# HBSTICK.net
KiCad netlist of a schematic drawn in EAGLE
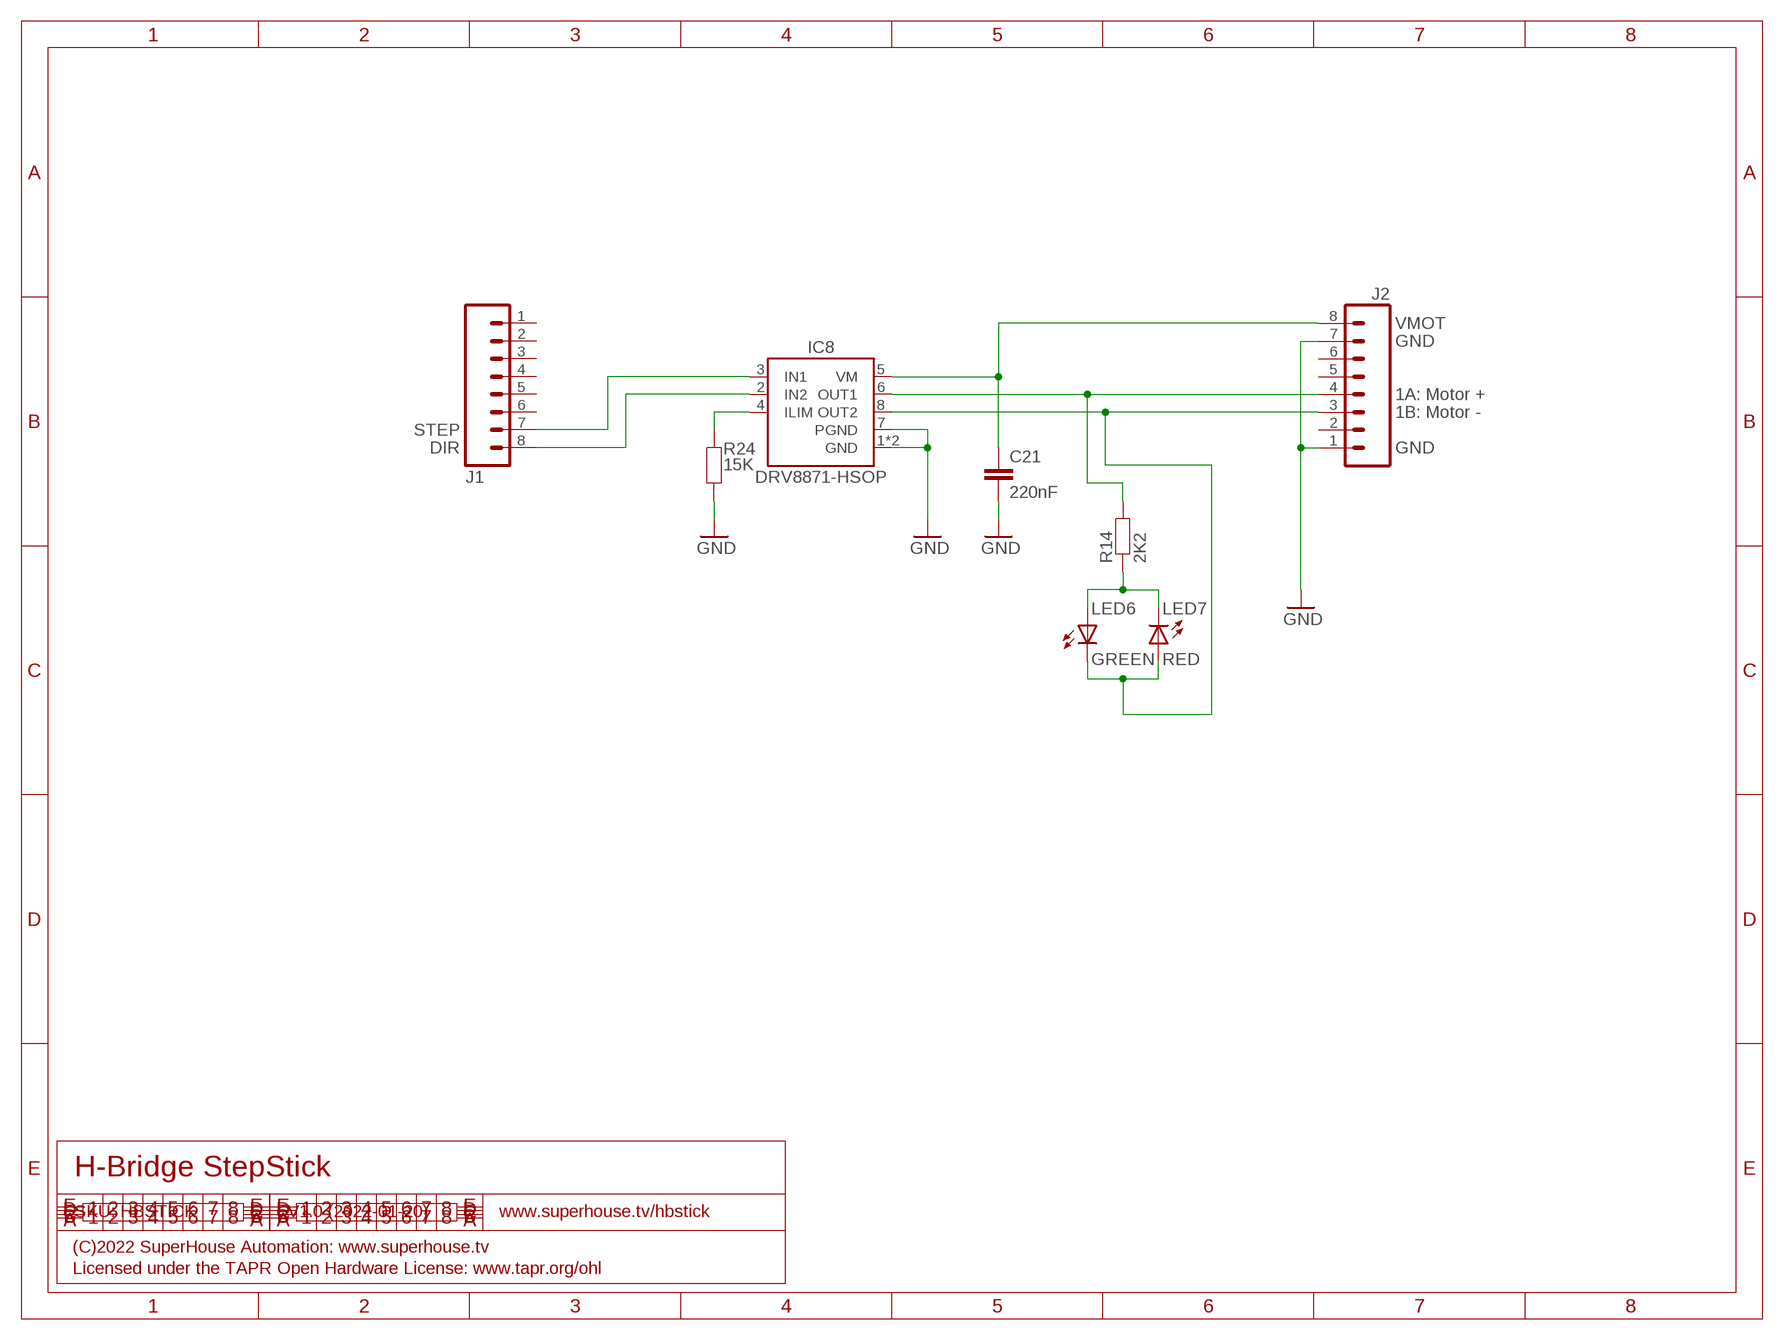
[diagram p0: schematic, sheet 1]

(export (version "E")
  (design (tool "Eeschema 10.0.6"))
  (components
    (comp (ref "C21")
      (value "220nF")
      (footprint "eagle-import:C0603")
      (libsource (lib "eagle-import") (part "CAP0603"))
    )
    (comp (ref "IC8")
      (value "DRV8871-HSOP")
      (footprint "eagle-import:SOIC8T")
      (libsource (lib "eagle-import") (part "DRV8871-HSOP"))
    )
    (comp (ref "J1")
      (value "M08-PIN-BELOW")
      (footprint "eagle-import:1X08-P-BELOW")
      (libsource (lib "eagle-import") (part "M08-PIN-BELOW"))
    )
    (comp (ref "J2")
      (value "M08-PIN-BELOW")
      (footprint "eagle-import:1X08-P-BELOW")
      (libsource (lib "eagle-import") (part "M08-PIN-BELOW"))
    )
    (comp (ref "LED6")
      (value "GREEN")
      (footprint "eagle-import:LED-0603")
      (libsource (lib "eagle-import") (part "LED0603"))
    )
    (comp (ref "LED7")
      (value "RED")
      (footprint "eagle-import:LED-0603")
      (libsource (lib "eagle-import") (part "LED0603"))
    )
    (comp (ref "R14")
      (value "2K2")
      (footprint "eagle-import:R0603")
      (libsource (lib "eagle-import") (part "RESISTOR0603"))
    )
    (comp (ref "R24")
      (value "15K")
      (footprint "eagle-import:R0603")
      (libsource (lib "eagle-import") (part "RESISTOR0603"))
    )
  )
  (nets
    (net (code "1") (name "GND") (class "Default")
      (node (ref "C21") (pin "2") (pinfunction "2_2") (pintype "passive"))
      (node (ref "IC8") (pin "1") (pinfunction "GND_1") (pintype "power_in"))
      (node (ref "IC8") (pin "7") (pinfunction "PGND_7") (pintype "passive"))
      (node (ref "IC8") (pin "TGND") (pinfunction "GND_TGND") (pintype "power_in"))
      (node (ref "J2") (pin "1") (pinfunction "1_1") (pintype "passive"))
      (node (ref "J2") (pin "7") (pinfunction "7_7") (pintype "passive"))
      (node (ref "R24") (pin "1") (pinfunction "1_1") (pintype "passive"))
    )
    (net (code "2") (name "Net-(IC8-ILIM)") (class "Default")
      (node (ref "IC8") (pin "4") (pinfunction "ILIM_4") (pintype "bidirectional"))
      (node (ref "R24") (pin "2") (pinfunction "2_2") (pintype "passive"))
    )
    (net (code "3") (name "Net-(IC8-IN1)") (class "Default")
      (node (ref "IC8") (pin "3") (pinfunction "IN1_3") (pintype "power_in"))
      (node (ref "J1") (pin "7") (pinfunction "7_7") (pintype "passive"))
    )
    (net (code "4") (name "Net-(IC8-IN2)") (class "Default")
      (node (ref "IC8") (pin "2") (pinfunction "IN2_2") (pintype "input"))
      (node (ref "J1") (pin "8") (pinfunction "8_8") (pintype "passive"))
    )
    (net (code "5") (name "Net-(IC8-OUT1)") (class "Default")
      (node (ref "IC8") (pin "6") (pinfunction "OUT1_6") (pintype "input"))
      (node (ref "J2") (pin "4") (pinfunction "4_4") (pintype "passive"))
      (node (ref "R14") (pin "2") (pinfunction "2_2") (pintype "passive"))
    )
    (net (code "6") (name "Net-(IC8-OUT2)") (class "Default")
      (node (ref "IC8") (pin "8") (pinfunction "OUT2_8") (pintype "input"))
      (node (ref "J2") (pin "3") (pinfunction "3_3") (pintype "passive"))
      (node (ref "LED6") (pin "C") (pinfunction "C_C") (pintype "passive"))
      (node (ref "LED7") (pin "A") (pinfunction "A_A") (pintype "passive"))
    )
    (net (code "7") (name "Net-(IC8-VM)") (class "Default")
      (node (ref "C21") (pin "1") (pinfunction "1_1") (pintype "passive"))
      (node (ref "IC8") (pin "5") (pinfunction "VM_5") (pintype "passive"))
      (node (ref "J2") (pin "8") (pinfunction "8_8") (pintype "passive"))
    )
    (net (code "8") (name "Net-(LED6-PadA)") (class "Default")
      (node (ref "LED6") (pin "A") (pinfunction "A_A") (pintype "passive"))
      (node (ref "LED7") (pin "C") (pinfunction "C_C") (pintype "passive"))
      (node (ref "R14") (pin "1") (pinfunction "1_1") (pintype "passive"))
    )
    (net (code "9") (name "unconnected-(J1-Pad1)") (class "Default")
      (node (ref "J1") (pin "1") (pinfunction "1_1") (pintype "passive"))
    )
    (net (code "10") (name "unconnected-(J1-Pad2)") (class "Default")
      (node (ref "J1") (pin "2") (pinfunction "2_2") (pintype "passive"))
    )
    (net (code "11") (name "unconnected-(J1-Pad3)") (class "Default")
      (node (ref "J1") (pin "3") (pinfunction "3_3") (pintype "passive"))
    )
    (net (code "12") (name "unconnected-(J1-Pad4)") (class "Default")
      (node (ref "J1") (pin "4") (pinfunction "4_4") (pintype "passive"))
    )
    (net (code "13") (name "unconnected-(J1-Pad5)") (class "Default")
      (node (ref "J1") (pin "5") (pinfunction "5_5") (pintype "passive"))
    )
    (net (code "14") (name "unconnected-(J1-Pad6)") (class "Default")
      (node (ref "J1") (pin "6") (pinfunction "6_6") (pintype "passive"))
    )
    (net (code "15") (name "unconnected-(J2-Pad2)") (class "Default")
      (node (ref "J2") (pin "2") (pinfunction "2_2") (pintype "passive"))
    )
    (net (code "16") (name "unconnected-(J2-Pad5)") (class "Default")
      (node (ref "J2") (pin "5") (pinfunction "5_5") (pintype "passive"))
    )
    (net (code "17") (name "unconnected-(J2-Pad6)") (class "Default")
      (node (ref "J2") (pin "6") (pinfunction "6_6") (pintype "passive"))
    )
  )
)
